# axiom_beta_imu_cso_v0_1_r1_1.net
KiCad netlist of a schematic drawn in EAGLE
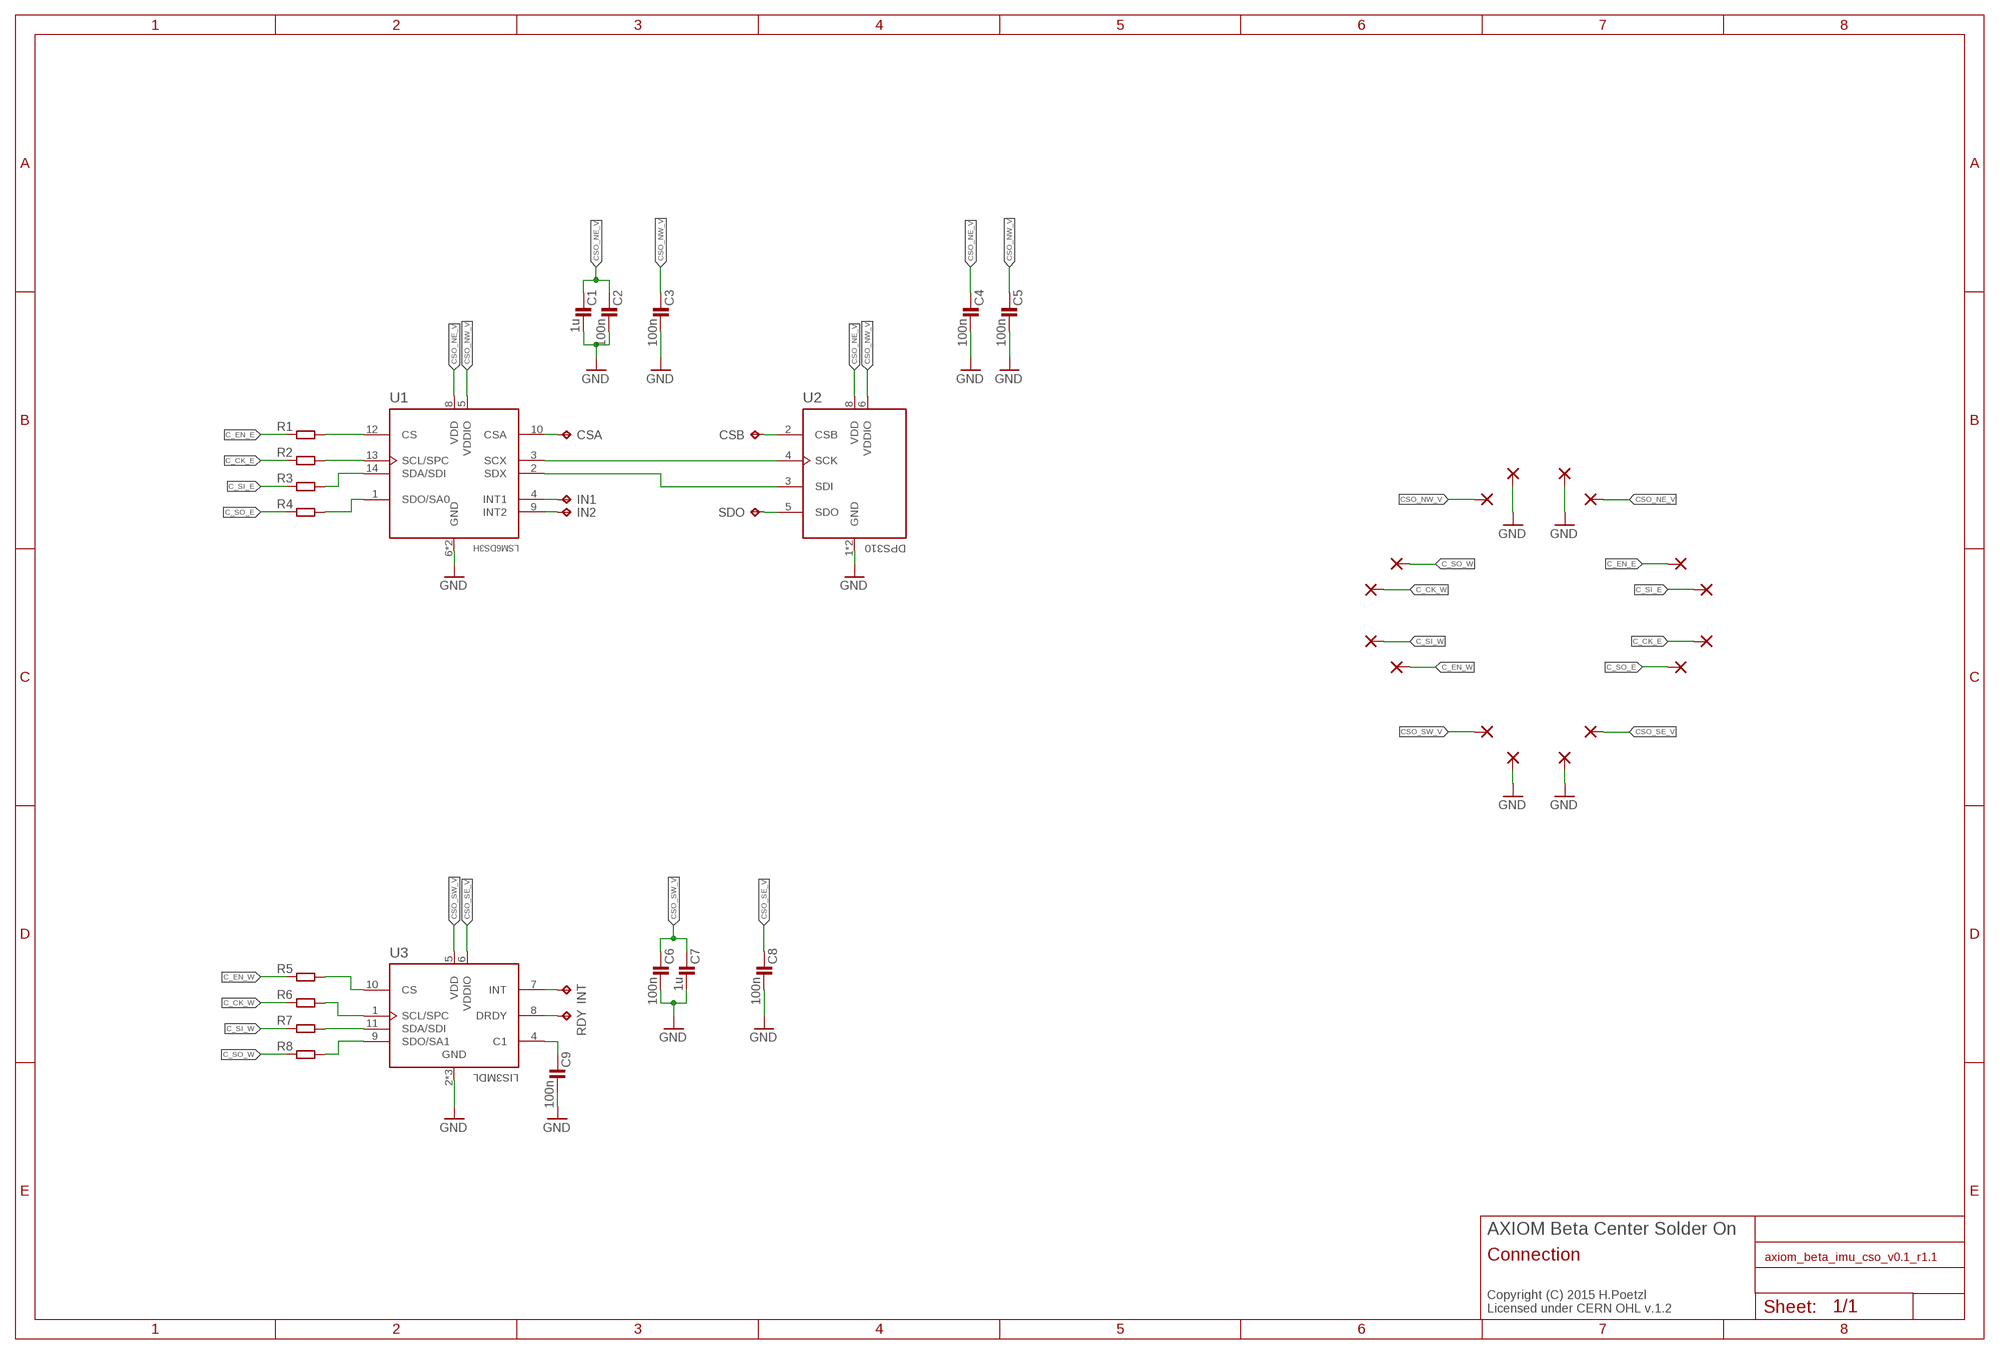
[diagram p0: schematic, sheet 1]

(export (version "E")
  (design (tool "Eeschema 10.0.6"))
  (components
    (comp (ref "C1")
      (value "1u")
      (footprint "eagle-import:0402-C")
      (libsource (lib "eagle-import") (part "C0402-C"))
    )
    (comp (ref "C2")
      (value "100n")
      (footprint "eagle-import:0402-C")
      (libsource (lib "eagle-import") (part "C0402-C"))
    )
    (comp (ref "C3")
      (value "100n")
      (footprint "eagle-import:0402-C")
      (libsource (lib "eagle-import") (part "C0402-C"))
    )
    (comp (ref "C4")
      (value "100n")
      (footprint "eagle-import:0402-C")
      (libsource (lib "eagle-import") (part "C0402-C"))
    )
    (comp (ref "C5")
      (value "100n")
      (footprint "eagle-import:0402-C")
      (libsource (lib "eagle-import") (part "C0402-C"))
    )
    (comp (ref "C6")
      (value "100n")
      (footprint "eagle-import:0402-C")
      (libsource (lib "eagle-import") (part "C0402-C"))
    )
    (comp (ref "C7")
      (value "1u")
      (footprint "eagle-import:0402-C")
      (libsource (lib "eagle-import") (part "C0402-C"))
    )
    (comp (ref "C8")
      (value "100n")
      (footprint "eagle-import:0402-C")
      (libsource (lib "eagle-import") (part "C0402-C"))
    )
    (comp (ref "C9")
      (value "100n")
      (footprint "eagle-import:0402-C")
      (libsource (lib "eagle-import") (part "C0402-C"))
    )
    (comp (ref "CSA")
      (value "TPTP06R")
      (footprint "eagle-import:TP06R")
      (libsource (lib "eagle-import") (part "TPTP06R"))
    )
    (comp (ref "CSB")
      (value "TPTP06R")
      (footprint "eagle-import:TP06R")
      (libsource (lib "eagle-import") (part "TPTP06R"))
    )
    (comp (ref "IN1")
      (value "TPTP06R")
      (footprint "eagle-import:TP06R")
      (libsource (lib "eagle-import") (part "TPTP06R"))
    )
    (comp (ref "IN2")
      (value "TPTP06R")
      (footprint "eagle-import:TP06R")
      (libsource (lib "eagle-import") (part "TPTP06R"))
    )
    (comp (ref "INT")
      (value "TPTP06R")
      (footprint "eagle-import:TP06R")
      (libsource (lib "eagle-import") (part "TPTP06R"))
    )
    (comp (ref "R1")
      (value "R0402-C")
      (footprint "eagle-import:0402-C")
      (libsource (lib "eagle-import") (part "R0402-C"))
    )
    (comp (ref "R2")
      (value "R0402-C")
      (footprint "eagle-import:0402-C")
      (libsource (lib "eagle-import") (part "R0402-C"))
    )
    (comp (ref "R3")
      (value "R0402-C")
      (footprint "eagle-import:0402-C")
      (libsource (lib "eagle-import") (part "R0402-C"))
    )
    (comp (ref "R4")
      (value "R0402-C")
      (footprint "eagle-import:0402-C")
      (libsource (lib "eagle-import") (part "R0402-C"))
    )
    (comp (ref "R5")
      (value "R0402-C")
      (footprint "eagle-import:0402-C")
      (libsource (lib "eagle-import") (part "R0402-C"))
    )
    (comp (ref "R6")
      (value "R0402-C")
      (footprint "eagle-import:0402-C")
      (libsource (lib "eagle-import") (part "R0402-C"))
    )
    (comp (ref "R7")
      (value "R0402-C")
      (footprint "eagle-import:0402-C")
      (libsource (lib "eagle-import") (part "R0402-C"))
    )
    (comp (ref "R8")
      (value "R0402-C")
      (footprint "eagle-import:0402-C")
      (libsource (lib "eagle-import") (part "R0402-C"))
    )
    (comp (ref "RDY")
      (value "TPTP06R")
      (footprint "eagle-import:TP06R")
      (libsource (lib "eagle-import") (part "TPTP06R"))
    )
    (comp (ref "SDO")
      (value "TPTP06R")
      (footprint "eagle-import:TP06R")
      (libsource (lib "eagle-import") (part "TPTP06R"))
    )
    (comp (ref "U$1")
      (value "PINPAD2.00MM")
      (footprint "eagle-import:1.4_0.8")
      (libsource (lib "eagle-import") (part "PINPAD2.00MM"))
    )
    (comp (ref "U$2")
      (value "PINPAD2.00MM")
      (footprint "eagle-import:1.4_0.8")
      (libsource (lib "eagle-import") (part "PINPAD2.00MM"))
    )
    (comp (ref "U$3")
      (value "PINPAD2.00MM")
      (footprint "eagle-import:1.4_0.8")
      (libsource (lib "eagle-import") (part "PINPAD2.00MM"))
    )
    (comp (ref "U$4")
      (value "PINPAD2.00MM")
      (footprint "eagle-import:1.4_0.8")
      (libsource (lib "eagle-import") (part "PINPAD2.00MM"))
    )
    (comp (ref "U$5")
      (value "PINPAD2.00MM")
      (footprint "eagle-import:1.4_0.8")
      (libsource (lib "eagle-import") (part "PINPAD2.00MM"))
    )
    (comp (ref "U$6")
      (value "PINPAD2.00MM")
      (footprint "eagle-import:1.4_0.8")
      (libsource (lib "eagle-import") (part "PINPAD2.00MM"))
    )
    (comp (ref "U$7")
      (value "PINPAD2.00MM")
      (footprint "eagle-import:1.4_0.8")
      (libsource (lib "eagle-import") (part "PINPAD2.00MM"))
    )
    (comp (ref "U$8")
      (value "PINPAD2.00MM")
      (footprint "eagle-import:1.4_0.8")
      (libsource (lib "eagle-import") (part "PINPAD2.00MM"))
    )
    (comp (ref "U$9")
      (value "PINPAD2.00MM")
      (footprint "eagle-import:1.4_0.8")
      (libsource (lib "eagle-import") (part "PINPAD2.00MM"))
    )
    (comp (ref "U$10")
      (value "PINPAD2.00MM")
      (footprint "eagle-import:1.4_0.8")
      (libsource (lib "eagle-import") (part "PINPAD2.00MM"))
    )
    (comp (ref "U$11")
      (value "PINPAD2.00MM")
      (footprint "eagle-import:1.4_0.8")
      (libsource (lib "eagle-import") (part "PINPAD2.00MM"))
    )
    (comp (ref "U$12")
      (value "PINPAD2.00MM")
      (footprint "eagle-import:1.4_0.8")
      (libsource (lib "eagle-import") (part "PINPAD2.00MM"))
    )
    (comp (ref "U$13")
      (value "PINPAD2.00MM")
      (footprint "eagle-import:1.4_0.8")
      (libsource (lib "eagle-import") (part "PINPAD2.00MM"))
    )
    (comp (ref "U$14")
      (value "PINPAD2.00MM")
      (footprint "eagle-import:1.4_0.8")
      (libsource (lib "eagle-import") (part "PINPAD2.00MM"))
    )
    (comp (ref "U$15")
      (value "PINPAD2.00MM")
      (footprint "eagle-import:1.4_0.8")
      (libsource (lib "eagle-import") (part "PINPAD2.00MM"))
    )
    (comp (ref "U$16")
      (value "PINPAD2.00MM")
      (footprint "eagle-import:1.4_0.8")
      (libsource (lib "eagle-import") (part "PINPAD2.00MM"))
    )
    (comp (ref "U1")
      (value "LSM6DS3H")
      (footprint "eagle-import:LGA-14L")
      (libsource (lib "eagle-import") (part "LSM6DS3H"))
    )
    (comp (ref "U2")
      (value "DPS310")
      (footprint "eagle-import:VLGA-8")
      (libsource (lib "eagle-import") (part "DPS310"))
    )
    (comp (ref "U3")
      (value "LIS3MDL")
      (footprint "eagle-import:VFLGA-12")
      (libsource (lib "eagle-import") (part "LIS3MDL"))
    )
  )
  (nets
    (net (code "1") (name "CSO_NE_V") (class "Default")
      (node (ref "C1") (pin "1") (pinfunction "1_1") (pintype "passive"))
      (node (ref "C2") (pin "1") (pinfunction "1_1") (pintype "passive"))
      (node (ref "C4") (pin "1") (pinfunction "1_1") (pintype "passive"))
      (node (ref "U$4") (pin "1") (pinfunction "P_1") (pintype "passive"))
      (node (ref "U1") (pin "8") (pinfunction "VDD_8") (pintype "power_in"))
      (node (ref "U2") (pin "8") (pinfunction "VDD_8") (pintype "power_in"))
    )
    (net (code "2") (name "CSO_NW_V") (class "Default")
      (node (ref "C3") (pin "1") (pinfunction "1_1") (pintype "passive"))
      (node (ref "C5") (pin "1") (pinfunction "1_1") (pintype "passive"))
      (node (ref "U$3") (pin "1") (pinfunction "P_1") (pintype "passive"))
      (node (ref "U1") (pin "5") (pinfunction "VDDIO_5") (pintype "power_in"))
      (node (ref "U2") (pin "6") (pinfunction "VDDIO_6") (pintype "power_in"))
    )
    (net (code "3") (name "CSO_SE_V") (class "Default")
      (node (ref "C8") (pin "1") (pinfunction "1_1") (pintype "passive"))
      (node (ref "U$14") (pin "1") (pinfunction "P_1") (pintype "passive"))
      (node (ref "U3") (pin "6") (pinfunction "VDDIO_6") (pintype "power_in"))
    )
    (net (code "4") (name "CSO_SW_V") (class "Default")
      (node (ref "C6") (pin "1") (pinfunction "1_1") (pintype "passive"))
      (node (ref "C7") (pin "1") (pinfunction "1_1") (pintype "passive"))
      (node (ref "U$13") (pin "1") (pinfunction "P_1") (pintype "passive"))
      (node (ref "U3") (pin "5") (pinfunction "VDD_5") (pintype "power_in"))
    )
    (net (code "5") (name "C_CK_E") (class "Default")
      (node (ref "R2") (pin "1") (pinfunction "1_1") (pintype "passive"))
      (node (ref "U$10") (pin "1") (pinfunction "P_1") (pintype "passive"))
    )
    (net (code "6") (name "C_CK_W") (class "Default")
      (node (ref "R6") (pin "1") (pinfunction "1_1") (pintype "passive"))
      (node (ref "U$7") (pin "1") (pinfunction "P_1") (pintype "passive"))
    )
    (net (code "7") (name "C_EN_E") (class "Default")
      (node (ref "R1") (pin "1") (pinfunction "1_1") (pintype "passive"))
      (node (ref "U$6") (pin "1") (pinfunction "P_1") (pintype "passive"))
    )
    (net (code "8") (name "C_EN_W") (class "Default")
      (node (ref "R5") (pin "1") (pinfunction "1_1") (pintype "passive"))
      (node (ref "U$11") (pin "1") (pinfunction "P_1") (pintype "passive"))
    )
    (net (code "9") (name "C_SI_E") (class "Default")
      (node (ref "R3") (pin "1") (pinfunction "1_1") (pintype "passive"))
      (node (ref "U$8") (pin "1") (pinfunction "P_1") (pintype "passive"))
    )
    (net (code "10") (name "C_SI_W") (class "Default")
      (node (ref "R7") (pin "1") (pinfunction "1_1") (pintype "passive"))
      (node (ref "U$9") (pin "1") (pinfunction "P_1") (pintype "passive"))
    )
    (net (code "11") (name "C_SO_E") (class "Default")
      (node (ref "R4") (pin "1") (pinfunction "1_1") (pintype "passive"))
      (node (ref "U$12") (pin "1") (pinfunction "P_1") (pintype "passive"))
    )
    (net (code "12") (name "C_SO_W") (class "Default")
      (node (ref "R8") (pin "1") (pinfunction "1_1") (pintype "passive"))
      (node (ref "U$5") (pin "1") (pinfunction "P_1") (pintype "passive"))
    )
    (net (code "13") (name "GND") (class "Default")
      (node (ref "C1") (pin "2") (pinfunction "2_2") (pintype "passive"))
      (node (ref "C2") (pin "2") (pinfunction "2_2") (pintype "passive"))
      (node (ref "C3") (pin "2") (pinfunction "2_2") (pintype "passive"))
      (node (ref "C4") (pin "2") (pinfunction "2_2") (pintype "passive"))
      (node (ref "C5") (pin "2") (pinfunction "2_2") (pintype "passive"))
      (node (ref "C6") (pin "2") (pinfunction "2_2") (pintype "passive"))
      (node (ref "C7") (pin "2") (pinfunction "2_2") (pintype "passive"))
      (node (ref "C8") (pin "2") (pinfunction "2_2") (pintype "passive"))
      (node (ref "C9") (pin "2") (pinfunction "2_2") (pintype "passive"))
      (node (ref "U$1") (pin "1") (pinfunction "P_1") (pintype "passive"))
      (node (ref "U$15") (pin "1") (pinfunction "P_1") (pintype "passive"))
      (node (ref "U$16") (pin "1") (pinfunction "P_1") (pintype "passive"))
      (node (ref "U$2") (pin "1") (pinfunction "P_1") (pintype "passive"))
      (node (ref "U1") (pin "6") (pinfunction "GND_6") (pintype "power_in"))
      (node (ref "U1") (pin "7") (pinfunction "GND_7") (pintype "power_in"))
      (node (ref "U2") (pin "1") (pinfunction "GND_1") (pintype "power_in"))
      (node (ref "U2") (pin "7") (pinfunction "GND_7") (pintype "power_in"))
      (node (ref "U3") (pin "12") (pinfunction "GND_12") (pintype "power_in"))
      (node (ref "U3") (pin "2") (pinfunction "GND_2") (pintype "power_in"))
      (node (ref "U3") (pin "3") (pinfunction "GND_3") (pintype "power_in"))
    )
    (net (code "14") (name "Net-(U1-CS)") (class "Default")
      (node (ref "R1") (pin "2") (pinfunction "2_2") (pintype "passive"))
      (node (ref "U1") (pin "12") (pinfunction "CS_12") (pintype "input"))
    )
    (net (code "15") (name "Net-(U1-CSA)") (class "Default")
      (node (ref "CSA") (pin "TP") (pinfunction "TP_TP") (pintype "input"))
      (node (ref "U1") (pin "10") (pinfunction "CSA_10") (pintype "input"))
    )
    (net (code "16") (name "Net-(U1-INT1)") (class "Default")
      (node (ref "IN1") (pin "TP") (pinfunction "TP_TP") (pintype "input"))
      (node (ref "U1") (pin "4") (pinfunction "INT1_4") (pintype "output"))
    )
    (net (code "17") (name "Net-(U1-INT2)") (class "Default")
      (node (ref "IN2") (pin "TP") (pinfunction "TP_TP") (pintype "input"))
      (node (ref "U1") (pin "9") (pinfunction "INT2_9") (pintype "bidirectional"))
    )
    (net (code "18") (name "Net-(U1-SCL{slash}SPC)") (class "Default")
      (node (ref "R2") (pin "2") (pinfunction "2_2") (pintype "passive"))
      (node (ref "U1") (pin "13") (pinfunction "SCL/SPC_13") (pintype "input"))
    )
    (net (code "19") (name "Net-(U1-SCX)") (class "Default")
      (node (ref "U1") (pin "3") (pinfunction "SCX_3") (pintype "bidirectional"))
      (node (ref "U2") (pin "4") (pinfunction "SCK_4") (pintype "input"))
    )
    (net (code "20") (name "Net-(U1-SDA{slash}SDI)") (class "Default")
      (node (ref "R3") (pin "2") (pinfunction "2_2") (pintype "passive"))
      (node (ref "U1") (pin "14") (pinfunction "SDA/SDI_14") (pintype "bidirectional"))
    )
    (net (code "21") (name "Net-(U1-SDO{slash}SA0)") (class "Default")
      (node (ref "R4") (pin "2") (pinfunction "2_2") (pintype "passive"))
      (node (ref "U1") (pin "1") (pinfunction "SDO/SA0_1") (pintype "bidirectional"))
    )
    (net (code "22") (name "Net-(U1-SDX)") (class "Default")
      (node (ref "U1") (pin "2") (pinfunction "SDX_2") (pintype "bidirectional"))
      (node (ref "U2") (pin "3") (pinfunction "SDI_3") (pintype "bidirectional"))
    )
    (net (code "23") (name "Net-(U2-CSB)") (class "Default")
      (node (ref "CSB") (pin "TP") (pinfunction "TP_TP") (pintype "input"))
      (node (ref "U2") (pin "2") (pinfunction "CSB_2") (pintype "input"))
    )
    (net (code "24") (name "Net-(U2-SDO)") (class "Default")
      (node (ref "SDO") (pin "TP") (pinfunction "TP_TP") (pintype "input"))
      (node (ref "U2") (pin "5") (pinfunction "SDO_5") (pintype "bidirectional"))
    )
    (net (code "25") (name "Net-(U3-C1)") (class "Default")
      (node (ref "C9") (pin "1") (pinfunction "1_1") (pintype "passive"))
      (node (ref "U3") (pin "4") (pinfunction "C1_4") (pintype "passive"))
    )
    (net (code "26") (name "Net-(U3-CS)") (class "Default")
      (node (ref "R5") (pin "2") (pinfunction "2_2") (pintype "passive"))
      (node (ref "U3") (pin "10") (pinfunction "CS_10") (pintype "input"))
    )
    (net (code "27") (name "Net-(U3-DRDY)") (class "Default")
      (node (ref "RDY") (pin "TP") (pinfunction "TP_TP") (pintype "input"))
      (node (ref "U3") (pin "8") (pinfunction "DRDY_8") (pintype "bidirectional"))
    )
    (net (code "28") (name "Net-(U3-INT)") (class "Default")
      (node (ref "INT") (pin "TP") (pinfunction "TP_TP") (pintype "input"))
      (node (ref "U3") (pin "7") (pinfunction "INT_7") (pintype "output"))
    )
    (net (code "29") (name "Net-(U3-SCL{slash}SPC)") (class "Default")
      (node (ref "R6") (pin "2") (pinfunction "2_2") (pintype "passive"))
      (node (ref "U3") (pin "1") (pinfunction "SCL/SPC_1") (pintype "input"))
    )
    (net (code "30") (name "Net-(U3-SDA{slash}SDI)") (class "Default")
      (node (ref "R7") (pin "2") (pinfunction "2_2") (pintype "passive"))
      (node (ref "U3") (pin "11") (pinfunction "SDA/SDI_11") (pintype "bidirectional"))
    )
    (net (code "31") (name "Net-(U3-SDO{slash}SA1)") (class "Default")
      (node (ref "R8") (pin "2") (pinfunction "2_2") (pintype "passive"))
      (node (ref "U3") (pin "9") (pinfunction "SDO/SA1_9") (pintype "bidirectional"))
    )
  )
)
